# display.net
KiCad netlist of a schematic drawn in EAGLE
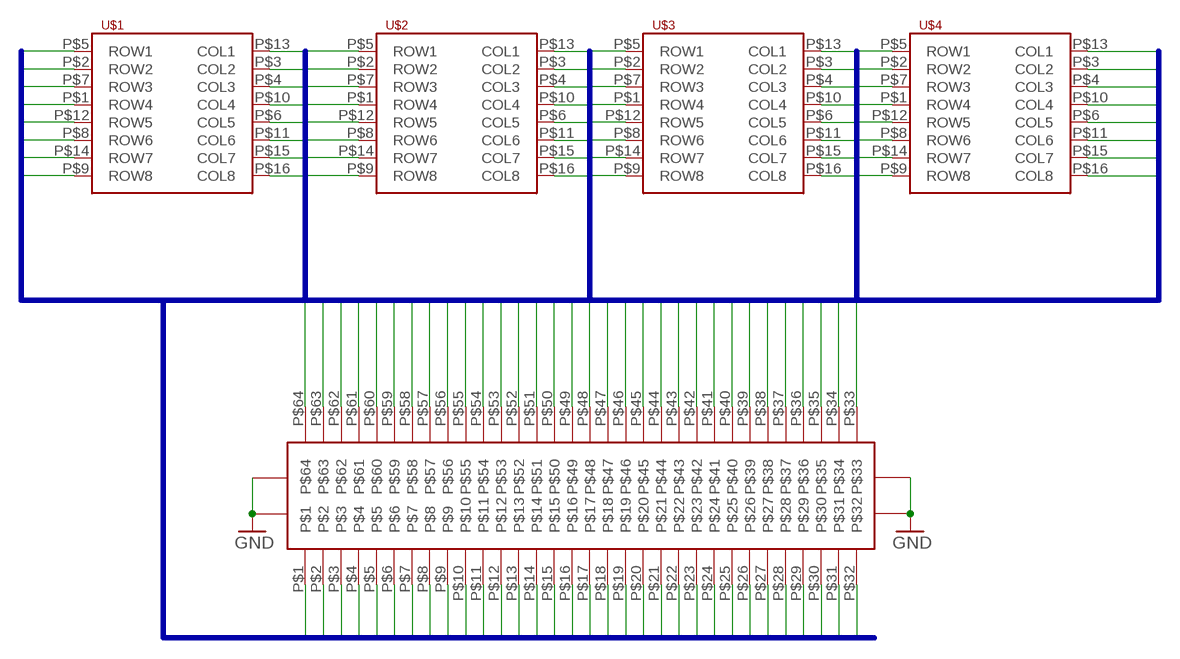
[diagram p0: schematic, sheet 1]

(export (version "E")
  (design (tool "Eeschema 10.0.6"))
  (components
    (comp (ref "U$1")
      (value "LED_8X8_MATRIX07088BH")
      (footprint "eagle-import:MATRIX_8X8_20MM")
      (libsource (lib "eagle-import") (part "LED_8X8_MATRIX07088BH"))
    )
    (comp (ref "U$2")
      (value "LED_8X8_MATRIX07088BH")
      (footprint "eagle-import:MATRIX_8X8_20MM")
      (libsource (lib "eagle-import") (part "LED_8X8_MATRIX07088BH"))
    )
    (comp (ref "U$3")
      (value "LED_8X8_MATRIX07088BH")
      (footprint "eagle-import:MATRIX_8X8_20MM")
      (libsource (lib "eagle-import") (part "LED_8X8_MATRIX07088BH"))
    )
    (comp (ref "U$4")
      (value "LED_8X8_MATRIX07088BH")
      (footprint "eagle-import:MATRIX_8X8_20MM")
      (libsource (lib "eagle-import") (part "LED_8X8_MATRIX07088BH"))
    )
    (comp (ref "U$5")
      (value "ANGLE_BOARD_CONNECTORONE_SIDED")
      (footprint "eagle-import:ONE_SIDED")
      (libsource (lib "eagle-import") (part "ANGLE_BOARD_CONNECTORONE_SIDED"))
    )
  )
  (nets
    (net (code "1") (name "/M1C1") (class "Default")
      (node (ref "U$1") (pin "P$13") (pinfunction "COL1_P$13") (pintype "bidirectional"))
      (node (ref "U$5") (pin "P$64") (pinfunction "P$64_P$64") (pintype "bidirectional"))
    )
    (net (code "2") (name "/M1C2") (class "Default")
      (node (ref "U$1") (pin "P$3") (pinfunction "COL2_P$3") (pintype "bidirectional"))
      (node (ref "U$5") (pin "P$63") (pinfunction "P$63_P$63") (pintype "bidirectional"))
    )
    (net (code "3") (name "/M1C3") (class "Default")
      (node (ref "U$1") (pin "P$4") (pinfunction "COL3_P$4") (pintype "bidirectional"))
      (node (ref "U$5") (pin "P$62") (pinfunction "P$62_P$62") (pintype "bidirectional"))
    )
    (net (code "4") (name "/M1C4") (class "Default")
      (node (ref "U$1") (pin "P$10") (pinfunction "COL4_P$10") (pintype "bidirectional"))
      (node (ref "U$5") (pin "P$61") (pinfunction "P$61_P$61") (pintype "bidirectional"))
    )
    (net (code "5") (name "/M1C5") (class "Default")
      (node (ref "U$1") (pin "P$6") (pinfunction "COL5_P$6") (pintype "bidirectional"))
      (node (ref "U$5") (pin "P$60") (pinfunction "P$60_P$60") (pintype "bidirectional"))
    )
    (net (code "6") (name "/M1C6") (class "Default")
      (node (ref "U$1") (pin "P$11") (pinfunction "COL6_P$11") (pintype "bidirectional"))
      (node (ref "U$5") (pin "P$59") (pinfunction "P$59_P$59") (pintype "bidirectional"))
    )
    (net (code "7") (name "/M1C7") (class "Default")
      (node (ref "U$1") (pin "P$15") (pinfunction "COL7_P$15") (pintype "bidirectional"))
      (node (ref "U$5") (pin "P$58") (pinfunction "P$58_P$58") (pintype "bidirectional"))
    )
    (net (code "8") (name "/M1C8") (class "Default")
      (node (ref "U$1") (pin "P$16") (pinfunction "COL8_P$16") (pintype "bidirectional"))
      (node (ref "U$5") (pin "P$57") (pinfunction "P$57_P$57") (pintype "bidirectional"))
    )
    (net (code "9") (name "/M1R1") (class "Default")
      (node (ref "U$1") (pin "P$5") (pinfunction "ROW1_P$5") (pintype "bidirectional"))
      (node (ref "U$5") (pin "P$1") (pinfunction "P$1_P$1") (pintype "bidirectional"))
    )
    (net (code "10") (name "/M1R2") (class "Default")
      (node (ref "U$1") (pin "P$2") (pinfunction "ROW2_P$2") (pintype "bidirectional"))
      (node (ref "U$5") (pin "P$2") (pinfunction "P$2_P$2") (pintype "bidirectional"))
    )
    (net (code "11") (name "/M1R3") (class "Default")
      (node (ref "U$1") (pin "P$7") (pinfunction "ROW3_P$7") (pintype "bidirectional"))
      (node (ref "U$5") (pin "P$3") (pinfunction "P$3_P$3") (pintype "bidirectional"))
    )
    (net (code "12") (name "/M1R4") (class "Default")
      (node (ref "U$1") (pin "P$1") (pinfunction "ROW4_P$1") (pintype "bidirectional"))
      (node (ref "U$5") (pin "P$4") (pinfunction "P$4_P$4") (pintype "bidirectional"))
    )
    (net (code "13") (name "/M1R5") (class "Default")
      (node (ref "U$1") (pin "P$12") (pinfunction "ROW5_P$12") (pintype "bidirectional"))
      (node (ref "U$5") (pin "P$5") (pinfunction "P$5_P$5") (pintype "bidirectional"))
    )
    (net (code "14") (name "/M1R6") (class "Default")
      (node (ref "U$1") (pin "P$8") (pinfunction "ROW6_P$8") (pintype "bidirectional"))
      (node (ref "U$5") (pin "P$6") (pinfunction "P$6_P$6") (pintype "bidirectional"))
    )
    (net (code "15") (name "/M1R7") (class "Default")
      (node (ref "U$1") (pin "P$14") (pinfunction "ROW7_P$14") (pintype "bidirectional"))
      (node (ref "U$5") (pin "P$7") (pinfunction "P$7_P$7") (pintype "bidirectional"))
    )
    (net (code "16") (name "/M1R8") (class "Default")
      (node (ref "U$1") (pin "P$9") (pinfunction "ROW8_P$9") (pintype "bidirectional"))
      (node (ref "U$5") (pin "P$8") (pinfunction "P$8_P$8") (pintype "bidirectional"))
    )
    (net (code "17") (name "/M2C1") (class "Default")
      (node (ref "U$2") (pin "P$13") (pinfunction "COL1_P$13") (pintype "bidirectional"))
      (node (ref "U$5") (pin "P$56") (pinfunction "P$56_P$56") (pintype "bidirectional"))
    )
    (net (code "18") (name "/M2C2") (class "Default")
      (node (ref "U$2") (pin "P$3") (pinfunction "COL2_P$3") (pintype "bidirectional"))
      (node (ref "U$5") (pin "P$55") (pinfunction "P$55_P$55") (pintype "bidirectional"))
    )
    (net (code "19") (name "/M2C3") (class "Default")
      (node (ref "U$2") (pin "P$4") (pinfunction "COL3_P$4") (pintype "bidirectional"))
      (node (ref "U$5") (pin "P$54") (pinfunction "P$54_P$54") (pintype "bidirectional"))
    )
    (net (code "20") (name "/M2C4") (class "Default")
      (node (ref "U$2") (pin "P$10") (pinfunction "COL4_P$10") (pintype "bidirectional"))
      (node (ref "U$5") (pin "P$53") (pinfunction "P$53_P$53") (pintype "bidirectional"))
    )
    (net (code "21") (name "/M2C5") (class "Default")
      (node (ref "U$2") (pin "P$6") (pinfunction "COL5_P$6") (pintype "bidirectional"))
      (node (ref "U$5") (pin "P$52") (pinfunction "P$52_P$52") (pintype "bidirectional"))
    )
    (net (code "22") (name "/M2C6") (class "Default")
      (node (ref "U$2") (pin "P$11") (pinfunction "COL6_P$11") (pintype "bidirectional"))
      (node (ref "U$5") (pin "P$51") (pinfunction "P$51_P$51") (pintype "bidirectional"))
    )
    (net (code "23") (name "/M2C7") (class "Default")
      (node (ref "U$2") (pin "P$15") (pinfunction "COL7_P$15") (pintype "bidirectional"))
      (node (ref "U$5") (pin "P$50") (pinfunction "P$50_P$50") (pintype "bidirectional"))
    )
    (net (code "24") (name "/M2C8") (class "Default")
      (node (ref "U$2") (pin "P$16") (pinfunction "COL8_P$16") (pintype "bidirectional"))
      (node (ref "U$5") (pin "P$49") (pinfunction "P$49_P$49") (pintype "bidirectional"))
    )
    (net (code "25") (name "/M2R1") (class "Default")
      (node (ref "U$2") (pin "P$5") (pinfunction "ROW1_P$5") (pintype "bidirectional"))
      (node (ref "U$5") (pin "P$9") (pinfunction "P$9_P$9") (pintype "bidirectional"))
    )
    (net (code "26") (name "/M2R2") (class "Default")
      (node (ref "U$2") (pin "P$2") (pinfunction "ROW2_P$2") (pintype "bidirectional"))
      (node (ref "U$5") (pin "P$10") (pinfunction "P$10_P$10") (pintype "bidirectional"))
    )
    (net (code "27") (name "/M2R3") (class "Default")
      (node (ref "U$2") (pin "P$7") (pinfunction "ROW3_P$7") (pintype "bidirectional"))
      (node (ref "U$5") (pin "P$11") (pinfunction "P$11_P$11") (pintype "bidirectional"))
    )
    (net (code "28") (name "/M2R4") (class "Default")
      (node (ref "U$2") (pin "P$1") (pinfunction "ROW4_P$1") (pintype "bidirectional"))
      (node (ref "U$5") (pin "P$12") (pinfunction "P$12_P$12") (pintype "bidirectional"))
    )
    (net (code "29") (name "/M2R5") (class "Default")
      (node (ref "U$2") (pin "P$12") (pinfunction "ROW5_P$12") (pintype "bidirectional"))
      (node (ref "U$5") (pin "P$13") (pinfunction "P$13_P$13") (pintype "bidirectional"))
    )
    (net (code "30") (name "/M2R6") (class "Default")
      (node (ref "U$2") (pin "P$8") (pinfunction "ROW6_P$8") (pintype "bidirectional"))
      (node (ref "U$5") (pin "P$14") (pinfunction "P$14_P$14") (pintype "bidirectional"))
    )
    (net (code "31") (name "/M2R7") (class "Default")
      (node (ref "U$2") (pin "P$14") (pinfunction "ROW7_P$14") (pintype "bidirectional"))
      (node (ref "U$5") (pin "P$15") (pinfunction "P$15_P$15") (pintype "bidirectional"))
    )
    (net (code "32") (name "/M2R8") (class "Default")
      (node (ref "U$2") (pin "P$9") (pinfunction "ROW8_P$9") (pintype "bidirectional"))
      (node (ref "U$5") (pin "P$16") (pinfunction "P$16_P$16") (pintype "bidirectional"))
    )
    (net (code "33") (name "/M3C1") (class "Default")
      (node (ref "U$3") (pin "P$13") (pinfunction "COL1_P$13") (pintype "bidirectional"))
      (node (ref "U$5") (pin "P$48") (pinfunction "P$48_P$48") (pintype "bidirectional"))
    )
    (net (code "34") (name "/M3C2") (class "Default")
      (node (ref "U$3") (pin "P$3") (pinfunction "COL2_P$3") (pintype "bidirectional"))
      (node (ref "U$5") (pin "P$47") (pinfunction "P$47_P$47") (pintype "bidirectional"))
    )
    (net (code "35") (name "/M3C3") (class "Default")
      (node (ref "U$3") (pin "P$4") (pinfunction "COL3_P$4") (pintype "bidirectional"))
      (node (ref "U$5") (pin "P$46") (pinfunction "P$46_P$46") (pintype "bidirectional"))
    )
    (net (code "36") (name "/M3C4") (class "Default")
      (node (ref "U$3") (pin "P$10") (pinfunction "COL4_P$10") (pintype "bidirectional"))
      (node (ref "U$5") (pin "P$45") (pinfunction "P$45_P$45") (pintype "bidirectional"))
    )
    (net (code "37") (name "/M3C5") (class "Default")
      (node (ref "U$3") (pin "P$6") (pinfunction "COL5_P$6") (pintype "bidirectional"))
      (node (ref "U$5") (pin "P$44") (pinfunction "P$44_P$44") (pintype "bidirectional"))
    )
    (net (code "38") (name "/M3C6") (class "Default")
      (node (ref "U$3") (pin "P$11") (pinfunction "COL6_P$11") (pintype "bidirectional"))
      (node (ref "U$5") (pin "P$43") (pinfunction "P$43_P$43") (pintype "bidirectional"))
    )
    (net (code "39") (name "/M3C7") (class "Default")
      (node (ref "U$3") (pin "P$15") (pinfunction "COL7_P$15") (pintype "bidirectional"))
      (node (ref "U$5") (pin "P$42") (pinfunction "P$42_P$42") (pintype "bidirectional"))
    )
    (net (code "40") (name "/M3C8") (class "Default")
      (node (ref "U$3") (pin "P$16") (pinfunction "COL8_P$16") (pintype "bidirectional"))
      (node (ref "U$5") (pin "P$41") (pinfunction "P$41_P$41") (pintype "bidirectional"))
    )
    (net (code "41") (name "/M3R1") (class "Default")
      (node (ref "U$3") (pin "P$5") (pinfunction "ROW1_P$5") (pintype "bidirectional"))
      (node (ref "U$5") (pin "P$17") (pinfunction "P$17_P$17") (pintype "bidirectional"))
    )
    (net (code "42") (name "/M3R2") (class "Default")
      (node (ref "U$3") (pin "P$2") (pinfunction "ROW2_P$2") (pintype "bidirectional"))
      (node (ref "U$5") (pin "P$18") (pinfunction "P$18_P$18") (pintype "bidirectional"))
    )
    (net (code "43") (name "/M3R3") (class "Default")
      (node (ref "U$3") (pin "P$7") (pinfunction "ROW3_P$7") (pintype "bidirectional"))
      (node (ref "U$5") (pin "P$19") (pinfunction "P$19_P$19") (pintype "bidirectional"))
    )
    (net (code "44") (name "/M3R4") (class "Default")
      (node (ref "U$3") (pin "P$1") (pinfunction "ROW4_P$1") (pintype "bidirectional"))
      (node (ref "U$5") (pin "P$20") (pinfunction "P$20_P$20") (pintype "bidirectional"))
    )
    (net (code "45") (name "/M3R5") (class "Default")
      (node (ref "U$3") (pin "P$12") (pinfunction "ROW5_P$12") (pintype "bidirectional"))
      (node (ref "U$5") (pin "P$21") (pinfunction "P$21_P$21") (pintype "bidirectional"))
    )
    (net (code "46") (name "/M3R6") (class "Default")
      (node (ref "U$3") (pin "P$8") (pinfunction "ROW6_P$8") (pintype "bidirectional"))
      (node (ref "U$5") (pin "P$22") (pinfunction "P$22_P$22") (pintype "bidirectional"))
    )
    (net (code "47") (name "/M3R7") (class "Default")
      (node (ref "U$3") (pin "P$14") (pinfunction "ROW7_P$14") (pintype "bidirectional"))
      (node (ref "U$5") (pin "P$23") (pinfunction "P$23_P$23") (pintype "bidirectional"))
    )
    (net (code "48") (name "/M3R8") (class "Default")
      (node (ref "U$3") (pin "P$9") (pinfunction "ROW8_P$9") (pintype "bidirectional"))
      (node (ref "U$5") (pin "P$24") (pinfunction "P$24_P$24") (pintype "bidirectional"))
    )
    (net (code "49") (name "/M4C1") (class "Default")
      (node (ref "U$4") (pin "P$13") (pinfunction "COL1_P$13") (pintype "bidirectional"))
      (node (ref "U$5") (pin "P$40") (pinfunction "P$40_P$40") (pintype "bidirectional"))
    )
    (net (code "50") (name "/M4C2") (class "Default")
      (node (ref "U$4") (pin "P$3") (pinfunction "COL2_P$3") (pintype "bidirectional"))
      (node (ref "U$5") (pin "P$39") (pinfunction "P$39_P$39") (pintype "bidirectional"))
    )
    (net (code "51") (name "/M4C3") (class "Default")
      (node (ref "U$4") (pin "P$4") (pinfunction "COL3_P$4") (pintype "bidirectional"))
      (node (ref "U$5") (pin "P$38") (pinfunction "P$38_P$38") (pintype "bidirectional"))
    )
    (net (code "52") (name "/M4C4") (class "Default")
      (node (ref "U$4") (pin "P$10") (pinfunction "COL4_P$10") (pintype "bidirectional"))
      (node (ref "U$5") (pin "P$37") (pinfunction "P$37_P$37") (pintype "bidirectional"))
    )
    (net (code "53") (name "/M4C5") (class "Default")
      (node (ref "U$4") (pin "P$6") (pinfunction "COL5_P$6") (pintype "bidirectional"))
      (node (ref "U$5") (pin "P$36") (pinfunction "P$36_P$36") (pintype "bidirectional"))
    )
    (net (code "54") (name "/M4C6") (class "Default")
      (node (ref "U$4") (pin "P$11") (pinfunction "COL6_P$11") (pintype "bidirectional"))
      (node (ref "U$5") (pin "P$35") (pinfunction "P$35_P$35") (pintype "bidirectional"))
    )
    (net (code "55") (name "/M4C7") (class "Default")
      (node (ref "U$4") (pin "P$15") (pinfunction "COL7_P$15") (pintype "bidirectional"))
      (node (ref "U$5") (pin "P$34") (pinfunction "P$34_P$34") (pintype "bidirectional"))
    )
    (net (code "56") (name "/M4C8") (class "Default")
      (node (ref "U$4") (pin "P$16") (pinfunction "COL8_P$16") (pintype "bidirectional"))
      (node (ref "U$5") (pin "P$33") (pinfunction "P$33_P$33") (pintype "bidirectional"))
    )
    (net (code "57") (name "/M4R1") (class "Default")
      (node (ref "U$4") (pin "P$5") (pinfunction "ROW1_P$5") (pintype "bidirectional"))
      (node (ref "U$5") (pin "P$25") (pinfunction "P$25_P$25") (pintype "bidirectional"))
    )
    (net (code "58") (name "/M4R2") (class "Default")
      (node (ref "U$4") (pin "P$2") (pinfunction "ROW2_P$2") (pintype "bidirectional"))
      (node (ref "U$5") (pin "P$26") (pinfunction "P$26_P$26") (pintype "bidirectional"))
    )
    (net (code "59") (name "/M4R3") (class "Default")
      (node (ref "U$4") (pin "P$7") (pinfunction "ROW3_P$7") (pintype "bidirectional"))
      (node (ref "U$5") (pin "P$27") (pinfunction "P$27_P$27") (pintype "bidirectional"))
    )
    (net (code "60") (name "/M4R4") (class "Default")
      (node (ref "U$4") (pin "P$1") (pinfunction "ROW4_P$1") (pintype "bidirectional"))
      (node (ref "U$5") (pin "P$28") (pinfunction "P$28_P$28") (pintype "bidirectional"))
    )
    (net (code "61") (name "/M4R5") (class "Default")
      (node (ref "U$4") (pin "P$12") (pinfunction "ROW5_P$12") (pintype "bidirectional"))
      (node (ref "U$5") (pin "P$29") (pinfunction "P$29_P$29") (pintype "bidirectional"))
    )
    (net (code "62") (name "/M4R6") (class "Default")
      (node (ref "U$4") (pin "P$8") (pinfunction "ROW6_P$8") (pintype "bidirectional"))
      (node (ref "U$5") (pin "P$30") (pinfunction "P$30_P$30") (pintype "bidirectional"))
    )
    (net (code "63") (name "/M4R7") (class "Default")
      (node (ref "U$4") (pin "P$14") (pinfunction "ROW7_P$14") (pintype "bidirectional"))
      (node (ref "U$5") (pin "P$31") (pinfunction "P$31_P$31") (pintype "bidirectional"))
    )
    (net (code "64") (name "/M4R8") (class "Default")
      (node (ref "U$4") (pin "P$9") (pinfunction "ROW8_P$9") (pintype "bidirectional"))
      (node (ref "U$5") (pin "P$32") (pinfunction "P$32_P$32") (pintype "bidirectional"))
    )
    (net (code "65") (name "GND") (class "Default")
      (node (ref "U$5") (pin "GND@1") (pinfunction "GND_GND@1") (pintype "bidirectional"))
      (node (ref "U$5") (pin "GND@2") (pinfunction "GND_GND@2") (pintype "bidirectional"))
      (node (ref "U$5") (pin "GND@3") (pinfunction "GND_GND@3") (pintype "bidirectional"))
      (node (ref "U$5") (pin "GND@4") (pinfunction "GND_GND@4") (pintype "bidirectional"))
    )
  )
)
